# Barebones_TQFP32.net
KiCad netlist of a schematic drawn in EAGLE
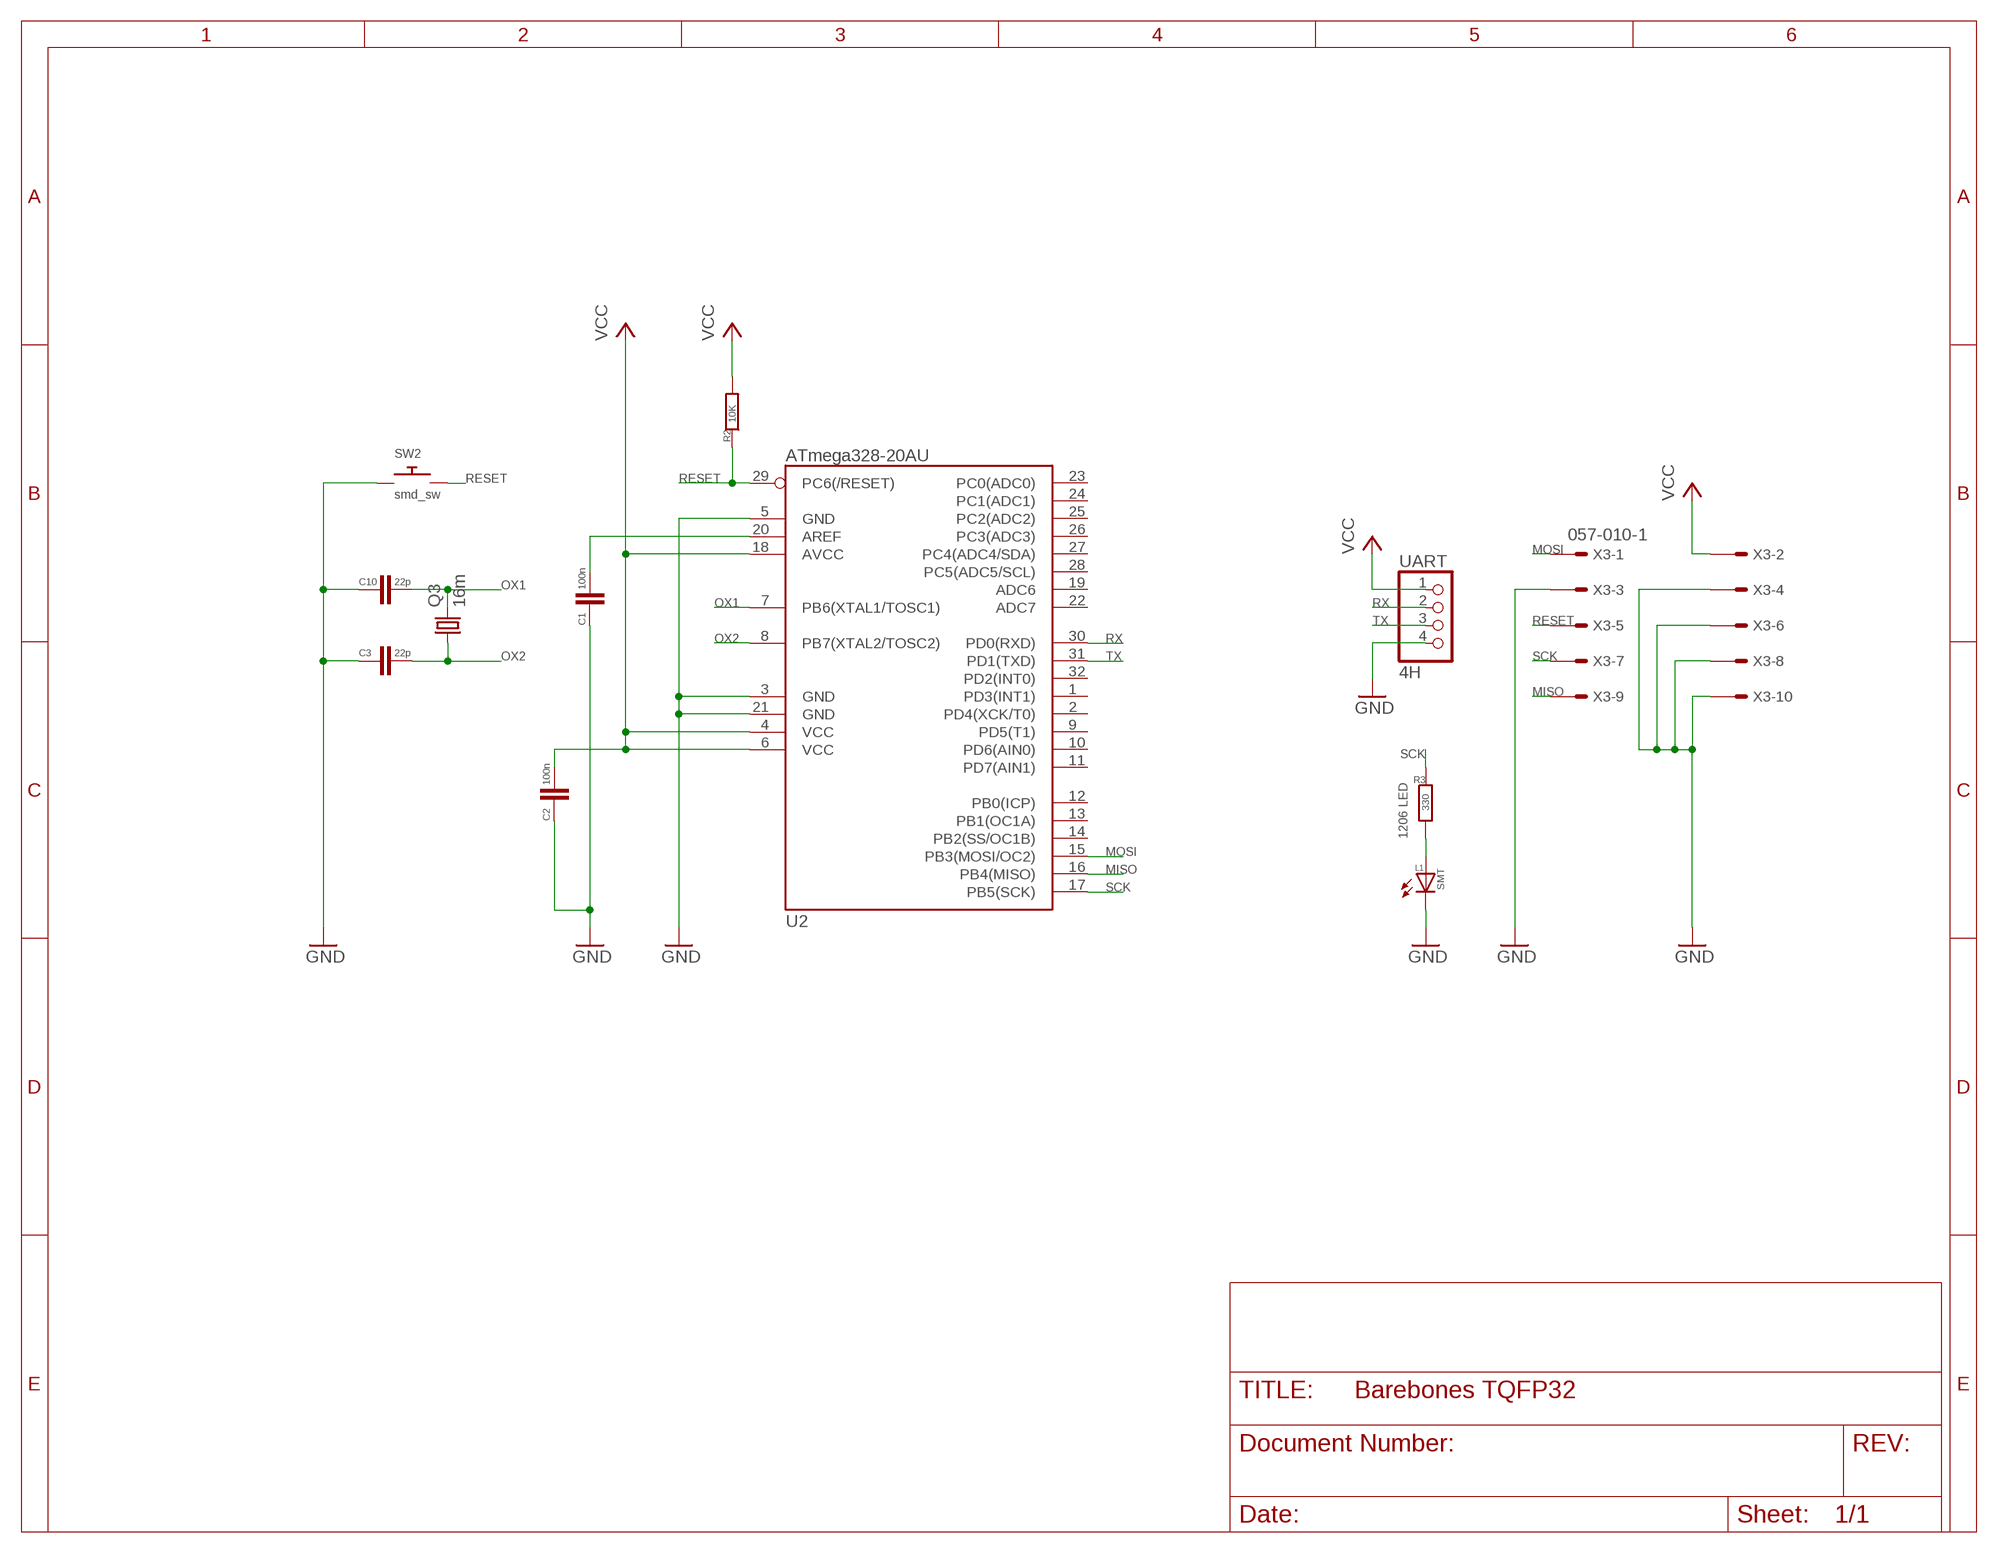
[diagram p0: schematic, sheet 1]

(export (version "E")
  (design (tool "Eeschema 10.0.6"))
  (components
    (comp (ref "C1")
      (value "100n")
      (footprint "eagle-import:C1206")
      (libsource (lib "eagle-import") (part "C-EUC1206"))
    )
    (comp (ref "C2")
      (value "100n")
      (footprint "eagle-import:C1206")
      (libsource (lib "eagle-import") (part "C-EUC1206"))
    )
    (comp (ref "C3")
      (value "22p")
      (footprint "eagle-import:C1206")
      (libsource (lib "eagle-import") (part "C-EUC1206"))
    )
    (comp (ref "C10")
      (value "22p")
      (footprint "eagle-import:C1206")
      (libsource (lib "eagle-import") (part "C-EUC1206"))
    )
    (comp (ref "L1")
      (value "SMT")
      (footprint "eagle-import:1206")
      (libsource (lib "eagle-import") (part "LEDSMT1206"))
    )
    (comp (ref "Q3")
      (value "16m")
      (footprint "eagle-import:HC49UP")
      (libsource (lib "eagle-import") (part "CRYSTALHC49UP"))
    )
    (comp (ref "R2")
      (value "10K")
      (footprint "eagle-import:R1206")
      (libsource (lib "eagle-import") (part "R-EU_R1206"))
    )
    (comp (ref "R3")
      (value "330")
      (footprint "eagle-import:R1206")
      (libsource (lib "eagle-import") (part "R-EU_R1206"))
    )
    (comp (ref "SW2")
      (value "smd_sw")
      (footprint "eagle-import:TACT_PANA-EVQ")
      (libsource (lib "eagle-import") (part "SWITCH_PUSHBUTTONEVQ-PE"))
    )
    (comp (ref "U2")
      (value "ATmega328-20AU")
      (footprint "eagle-import:TQFP32")
      (libsource (lib "eagle-import") (part "ATMEGA168"))
    )
    (comp (ref "UART")
      (value "4H")
      (footprint "eagle-import:1X04")
      (libsource (lib "eagle-import") (part "PINHD-1X4"))
    )
    (comp (ref "X3")
      (value "057-010-1")
      (footprint "eagle-import:057-010-1")
      (libsource (lib "eagle-import") (part "057-010-1"))
    )
  )
  (nets
    (net (code "1") (name "/MISO") (class "Default")
      (node (ref "U2") (pin "16") (pinfunction "PB4(MISO)_16") (pintype "bidirectional"))
      (node (ref "X3") (pin "9") (pinfunction "S_9") (pintype "passive"))
    )
    (net (code "2") (name "/MOSI") (class "Default")
      (node (ref "U2") (pin "15") (pinfunction "PB3(MOSI/OC2)_15") (pintype "bidirectional"))
      (node (ref "X3") (pin "1") (pinfunction "S_1") (pintype "passive"))
    )
    (net (code "3") (name "/OX1") (class "Default")
      (node (ref "C10") (pin "2") (pinfunction "2_2") (pintype "passive"))
      (node (ref "Q3") (pin "2") (pinfunction "2_2") (pintype "passive"))
      (node (ref "U2") (pin "7") (pinfunction "PB6(XTAL1/TOSC1)_7") (pintype "bidirectional"))
    )
    (net (code "4") (name "/OX2") (class "Default")
      (node (ref "C3") (pin "2") (pinfunction "2_2") (pintype "passive"))
      (node (ref "Q3") (pin "1") (pinfunction "1_1") (pintype "passive"))
      (node (ref "U2") (pin "8") (pinfunction "PB7(XTAL2/TOSC2)_8") (pintype "bidirectional"))
    )
    (net (code "5") (name "/RESET") (class "Default")
      (node (ref "R2") (pin "1") (pinfunction "1_1") (pintype "passive"))
      (node (ref "SW2") (pin "P$2") (pinfunction "P$2_P$2") (pintype "passive"))
      (node (ref "U2") (pin "29") (pinfunction "PC6(/RESET)_29") (pintype "bidirectional"))
      (node (ref "X3") (pin "5") (pinfunction "S_5") (pintype "passive"))
    )
    (net (code "6") (name "/RX") (class "Default")
      (node (ref "U2") (pin "30") (pinfunction "PD0(RXD)_30") (pintype "bidirectional"))
      (node (ref "UART") (pin "2") (pinfunction "2_2") (pintype "passive"))
    )
    (net (code "7") (name "/SCK") (class "Default")
      (node (ref "R3") (pin "1") (pinfunction "1_1") (pintype "passive"))
      (node (ref "U2") (pin "17") (pinfunction "PB5(SCK)_17") (pintype "bidirectional"))
      (node (ref "X3") (pin "7") (pinfunction "S_7") (pintype "passive"))
    )
    (net (code "8") (name "/TX") (class "Default")
      (node (ref "U2") (pin "31") (pinfunction "PD1(TXD)_31") (pintype "bidirectional"))
      (node (ref "UART") (pin "3") (pinfunction "3_3") (pintype "passive"))
    )
    (net (code "9") (name "GND") (class "Default")
      (node (ref "C1") (pin "1") (pinfunction "1_1") (pintype "passive"))
      (node (ref "C10") (pin "1") (pinfunction "1_1") (pintype "passive"))
      (node (ref "C2") (pin "1") (pinfunction "1_1") (pintype "passive"))
      (node (ref "C3") (pin "1") (pinfunction "1_1") (pintype "passive"))
      (node (ref "L1") (pin "C") (pinfunction "C_C") (pintype "passive"))
      (node (ref "SW2") (pin "P$1") (pinfunction "P$1_P$1") (pintype "passive"))
      (node (ref "U2") (pin "21") (pinfunction "GND_21") (pintype "bidirectional"))
      (node (ref "U2") (pin "3") (pinfunction "GND_3") (pintype "bidirectional"))
      (node (ref "U2") (pin "5") (pinfunction "GND_5") (pintype "bidirectional"))
      (node (ref "UART") (pin "4") (pinfunction "4_4") (pintype "passive"))
      (node (ref "X3") (pin "10") (pinfunction "S_10") (pintype "passive"))
      (node (ref "X3") (pin "3") (pinfunction "S_3") (pintype "passive"))
      (node (ref "X3") (pin "4") (pinfunction "S_4") (pintype "passive"))
      (node (ref "X3") (pin "6") (pinfunction "S_6") (pintype "passive"))
      (node (ref "X3") (pin "8") (pinfunction "S_8") (pintype "passive"))
    )
    (net (code "10") (name "Net-(L1-PadA)") (class "Default")
      (node (ref "L1") (pin "A") (pinfunction "A_A") (pintype "passive"))
      (node (ref "R3") (pin "2") (pinfunction "2_2") (pintype "passive"))
    )
    (net (code "11") (name "Net-(U2-AREF)") (class "Default")
      (node (ref "C1") (pin "2") (pinfunction "2_2") (pintype "passive"))
      (node (ref "U2") (pin "20") (pinfunction "AREF_20") (pintype "bidirectional"))
    )
    (net (code "12") (name "VCC") (class "Default")
      (node (ref "C2") (pin "2") (pinfunction "2_2") (pintype "passive"))
      (node (ref "R2") (pin "2") (pinfunction "2_2") (pintype "passive"))
      (node (ref "U2") (pin "18") (pinfunction "AVCC_18") (pintype "bidirectional"))
      (node (ref "U2") (pin "4") (pinfunction "VCC_4") (pintype "bidirectional"))
      (node (ref "U2") (pin "6") (pinfunction "VCC_6") (pintype "bidirectional"))
      (node (ref "UART") (pin "1") (pinfunction "1_1") (pintype "passive"))
      (node (ref "X3") (pin "2") (pinfunction "S_2") (pintype "passive"))
    )
    (net (code "13") (name "unconnected-(U2-ADC6-Pad19)") (class "Default")
      (node (ref "U2") (pin "19") (pinfunction "ADC6_19") (pintype "bidirectional"))
    )
    (net (code "14") (name "unconnected-(U2-ADC7-Pad22)") (class "Default")
      (node (ref "U2") (pin "22") (pinfunction "ADC7_22") (pintype "bidirectional"))
    )
    (net (code "15") (name "unconnected-(U2-PB0(ICP)-Pad12)") (class "Default")
      (node (ref "U2") (pin "12") (pinfunction "PB0(ICP)_12") (pintype "bidirectional"))
    )
    (net (code "16") (name "unconnected-(U2-PB1(OC1A)-Pad13)") (class "Default")
      (node (ref "U2") (pin "13") (pinfunction "PB1(OC1A)_13") (pintype "bidirectional"))
    )
    (net (code "17") (name "unconnected-(U2-PB2(SS{slash}OC1B)-Pad14)") (class "Default")
      (node (ref "U2") (pin "14") (pinfunction "PB2(SS/OC1B)_14") (pintype "bidirectional"))
    )
    (net (code "18") (name "unconnected-(U2-PC0(ADC0)-Pad23)") (class "Default")
      (node (ref "U2") (pin "23") (pinfunction "PC0(ADC0)_23") (pintype "bidirectional"))
    )
    (net (code "19") (name "unconnected-(U2-PC1(ADC1)-Pad24)") (class "Default")
      (node (ref "U2") (pin "24") (pinfunction "PC1(ADC1)_24") (pintype "bidirectional"))
    )
    (net (code "20") (name "unconnected-(U2-PC2(ADC2)-Pad25)") (class "Default")
      (node (ref "U2") (pin "25") (pinfunction "PC2(ADC2)_25") (pintype "bidirectional"))
    )
    (net (code "21") (name "unconnected-(U2-PC3(ADC3)-Pad26)") (class "Default")
      (node (ref "U2") (pin "26") (pinfunction "PC3(ADC3)_26") (pintype "bidirectional"))
    )
    (net (code "22") (name "unconnected-(U2-PC4(ADC4{slash}SDA)-Pad27)") (class "Default")
      (node (ref "U2") (pin "27") (pinfunction "PC4(ADC4/SDA)_27") (pintype "bidirectional"))
    )
    (net (code "23") (name "unconnected-(U2-PC5(ADC5{slash}SCL)-Pad28)") (class "Default")
      (node (ref "U2") (pin "28") (pinfunction "PC5(ADC5/SCL)_28") (pintype "bidirectional"))
    )
    (net (code "24") (name "unconnected-(U2-PD2(INT0)-Pad32)") (class "Default")
      (node (ref "U2") (pin "32") (pinfunction "PD2(INT0)_32") (pintype "bidirectional"))
    )
    (net (code "25") (name "unconnected-(U2-PD3(INT1)-Pad1)") (class "Default")
      (node (ref "U2") (pin "1") (pinfunction "PD3(INT1)_1") (pintype "bidirectional"))
    )
    (net (code "26") (name "unconnected-(U2-PD4(XCK{slash}T0)-Pad2)") (class "Default")
      (node (ref "U2") (pin "2") (pinfunction "PD4(XCK/T0)_2") (pintype "bidirectional"))
    )
    (net (code "27") (name "unconnected-(U2-PD5(T1)-Pad9)") (class "Default")
      (node (ref "U2") (pin "9") (pinfunction "PD5(T1)_9") (pintype "bidirectional"))
    )
    (net (code "28") (name "unconnected-(U2-PD6(AIN0)-Pad10)") (class "Default")
      (node (ref "U2") (pin "10") (pinfunction "PD6(AIN0)_10") (pintype "bidirectional"))
    )
    (net (code "29") (name "unconnected-(U2-PD7(AIN1)-Pad11)") (class "Default")
      (node (ref "U2") (pin "11") (pinfunction "PD7(AIN1)_11") (pintype "bidirectional"))
    )
  )
)
